# 1PCB_Shematic.net
KiCad netlist of a schematic drawn in Altium Designer
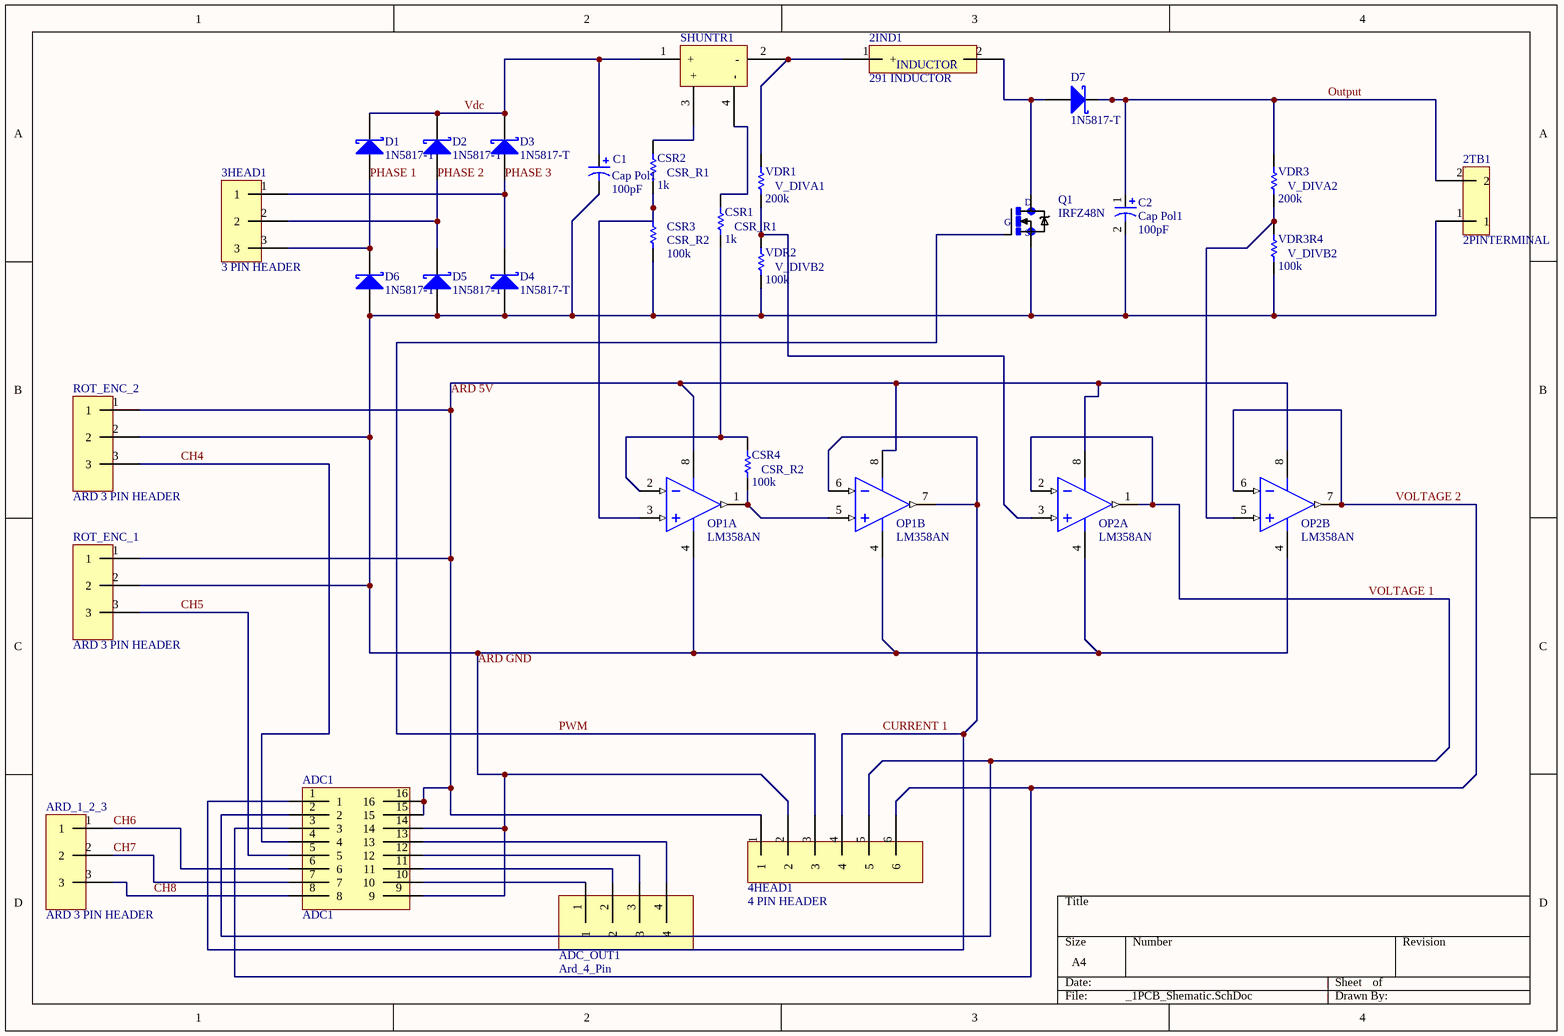
[diagram p0: _1PCB_Shematic.SchDoc]

(export (version "E")
  (design (tool "Eeschema 10.0.6"))
  (components
    (comp (ref "2IND1")
      (value "291 INDUCTOR")
      (footprint "3 CM INDUCTOR")
      (libsource (lib "CUSTOM IND") (part "2IND?"))
    )
    (comp (ref "2TB1")
      (value "2PINTERMINAL")
      (footprint "2 PIN TERMINAL BLOCK")
      (libsource (lib "altium-import") (part "root_1_2TB?_"))
    )
    (comp (ref "3HEAD1")
      (value "3 PIN HEADER")
      (footprint "3 PIN HEADER")
      (libsource (lib "3PINHEADER") (part "3HEAD?"))
    )
    (comp (ref "4HEAD1")
      (value "4 PIN HEADER")
      (footprint "4 PIN HEADER")
      (libsource (lib "4PINHEADER") (part "4HEAD?"))
    )
    (comp (ref "ADC1")
      (value "ADC1")
      (footprint "PDIP16_300MC")
      (libsource (lib "altium-import") (part "root_0_MCP3008_"))
    )
    (comp (ref "ADC_OUT1")
      (value "Ard_4_Pin")
      (footprint "ARD_4_PIN")
      (libsource (lib "altium-import") (part "root_0_APIN?_"))
    )
    (comp (ref "ARD_1_2_3")
      (value "ARD 3 PIN HEADER")
      (footprint "ARD 3 PIN HEADER")
      (libsource (lib "altium-import") (part "root_3_ARD_3_PIN?_"))
    )
    (comp (ref "C1")
      (value "Cap Pol1")
      (footprint "PCBComponent_1")
      (description "Polarized Capacitor (Radial)")
      (fields (field (name "ALTIUM_VALUE") "100pF") (field (name "PUBLISHER") "Altium Limited"))
      (libsource (lib "") (part "Cap Pol1_1"))
    )
    (comp (ref "C2")
      (value "Cap Pol1")
      (footprint "Copy of cap:PCBComponent_1")
      (description "Polarized Capacitor (Radial)")
      (fields (field (name "ALTIUM_VALUE") "100pF") (field (name "PUBLISHER") "Altium Limited"))
      (libsource (lib "Miscellaneous Devices") (part "Cap Pol1"))
    )
    (comp (ref "CSR1")
      (value "CSR_R1")
      (footprint "AXIAL-0.3")
      (description "Resistor")
      (fields (field (name "ALTIUM_VALUE") "1k") (field (name "PUBLISHER") "Altium Limited"))
      (libsource (lib "Miscellaneous Devices") (part "Res1"))
    )
    (comp (ref "CSR2")
      (value "CSR_R1")
      (footprint "AXIAL-0.3")
      (description "Resistor")
      (fields (field (name "ALTIUM_VALUE") "1k") (field (name "PUBLISHER") "Altium Limited"))
      (libsource (lib "Miscellaneous Devices") (part "Res1"))
    )
    (comp (ref "CSR3")
      (value "CSR_R2")
      (footprint "AXIAL-0.3")
      (description "Resistor")
      (fields (field (name "ALTIUM_VALUE") "100k") (field (name "PUBLISHER") "Altium Limited"))
      (libsource (lib "Miscellaneous Devices") (part "Res1"))
    )
    (comp (ref "CSR4")
      (value "CSR_R2")
      (footprint "AXIAL-0.3")
      (description "Resistor")
      (fields (field (name "ALTIUM_VALUE") "100k") (field (name "PUBLISHER") "Altium Limited"))
      (libsource (lib "Miscellaneous Devices") (part "Res1"))
    )
    (comp (ref "D1")
      (value "1N5817-T")
      (footprint "DIOD-DO-41-P-2")
      (description "Schottky Barrier Rectifier, 1 A, 20 V, -65 to 125 degC, 2-Pin DO-41, RoHS, Tape and Reel")
      (fields (field (name "MANUFACTURER") "DiodesIncorporated"))
      (libsource (lib "Altium Content Vault") (part "DSKY-AK-2"))
    )
    (comp (ref "D2")
      (value "1N5817-T")
      (footprint "DIOD-DO-41-P-2")
      (description "Schottky Barrier Rectifier, 1 A, 20 V, -65 to 125 degC, 2-Pin DO-41, RoHS, Tape and Reel")
      (fields (field (name "MANUFACTURER") "DiodesIncorporated"))
      (libsource (lib "Altium Content Vault") (part "DSKY-AK-2"))
    )
    (comp (ref "D3")
      (value "1N5817-T")
      (footprint "DIOD-DO-41-P-2")
      (description "Schottky Barrier Rectifier, 1 A, 20 V, -65 to 125 degC, 2-Pin DO-41, RoHS, Tape and Reel")
      (fields (field (name "MANUFACTURER") "DiodesIncorporated"))
      (libsource (lib "Altium Content Vault") (part "DSKY-AK-2"))
    )
    (comp (ref "D4")
      (value "1N5817-T")
      (footprint "DIOD-DO-41-P-2")
      (description "Schottky Barrier Rectifier, 1 A, 20 V, -65 to 125 degC, 2-Pin DO-41, RoHS, Tape and Reel")
      (fields (field (name "MANUFACTURER") "DiodesIncorporated"))
      (libsource (lib "Altium Content Vault") (part "DSKY-AK-2"))
    )
    (comp (ref "D5")
      (value "1N5817-T")
      (footprint "DIOD-DO-41-P-2")
      (description "Schottky Barrier Rectifier, 1 A, 20 V, -65 to 125 degC, 2-Pin DO-41, RoHS, Tape and Reel")
      (fields (field (name "MANUFACTURER") "DiodesIncorporated"))
      (libsource (lib "Altium Content Vault") (part "DSKY-AK-2"))
    )
    (comp (ref "D6")
      (value "1N5817-T")
      (footprint "DIOD-DO-41-P-2")
      (description "Schottky Barrier Rectifier, 1 A, 20 V, -65 to 125 degC, 2-Pin DO-41, RoHS, Tape and Reel")
      (fields (field (name "MANUFACTURER") "DiodesIncorporated"))
      (libsource (lib "Altium Content Vault") (part "DSKY-AK-2"))
    )
    (comp (ref "D7")
      (value "1N5817-T")
      (footprint "DIOD-DO-41-P-2")
      (description "Schottky Barrier Rectifier, 1 A, 20 V, -65 to 125 degC, 2-Pin DO-41, RoHS, Tape and Reel")
      (fields (field (name "MANUFACTURER") "DiodesIncorporated"))
      (libsource (lib "Altium Content Vault") (part "DSKY-AK-2"))
    )
    (comp (ref "OP1")
      (value "LM358AN")
      (footprint "N08E")
      (description "Low Power Dual Operational Amplifier, 8-pin MDIP")
      (fields (field (name "MANUFACTURER") "National Semiconductor"))
      (libsource (lib "Altium Content Vault") (part "AMP-OPA-LM158-8"))
    )
    (comp (ref "OP2")
      (value "LM358AN")
      (footprint "N08E")
      (description "Low Power Dual Operational Amplifier, 8-pin MDIP")
      (fields (field (name "MANUFACTURER") "National Semiconductor"))
      (libsource (lib "Altium Content Vault") (part "AMP-OPA-LM158-8"))
    )
    (comp (ref "Q1")
      (value "IRFZ48N")
      (footprint "TO220BV_IRFZ48N(Primary)")
      (description "55V Single N-Channel HEXFET Power MOSFET in a TO-220AB package")
      (fields (field (name "MF") "International Rectifier"))
      (libsource (lib "IRFZ48N") (part "IRFZ48N"))
    )
    (comp (ref "ROT_ENC_1")
      (value "ARD 3 PIN HEADER")
      (footprint "ARD 3 PIN HEADER")
      (libsource (lib "altium-import") (part "root_3_ARD_3_PIN?_"))
    )
    (comp (ref "ROT_ENC_2")
      (value "ARD 3 PIN HEADER")
      (footprint "ARD 3 PIN HEADER")
      (libsource (lib "altium-import") (part "root_3_ARD_3_PIN?_"))
    )
    (comp (ref "SHUNTR1")
      (value "~")
      (footprint "SHUNT15.24")
      (libsource (lib "SHUNT RESISTOR") (part "SHUNTR?"))
    )
    (comp (ref "VDR1")
      (value "V_DIVA1")
      (footprint "AXIAL-0.3")
      (description "Resistor")
      (fields (field (name "ALTIUM_VALUE") "200k") (field (name "PUBLISHER") "Altium Limited"))
      (libsource (lib "Miscellaneous Devices") (part "Res1"))
    )
    (comp (ref "VDR2")
      (value "V_DIVB2")
      (footprint "AXIAL-0.3")
      (description "Resistor")
      (fields (field (name "ALTIUM_VALUE") "100k") (field (name "PUBLISHER") "Altium Limited"))
      (libsource (lib "Miscellaneous Devices") (part "Res1"))
    )
    (comp (ref "VDR3")
      (value "V_DIVA2")
      (footprint "AXIAL-0.3")
      (description "Resistor")
      (fields (field (name "ALTIUM_VALUE") "200k") (field (name "PUBLISHER") "Altium Limited"))
      (libsource (lib "Miscellaneous Devices") (part "Res1"))
    )
    (comp (ref "VDR3R4")
      (value "V_DIVB2")
      (footprint "AXIAL-0.3")
      (description "Resistor")
      (fields (field (name "ALTIUM_VALUE") "100k") (field (name "PUBLISHER") "Altium Limited"))
      (libsource (lib "Miscellaneous Devices") (part "Res1"))
    )
  )
  (nets
    (net (code "1") (name "/ARD 5V") (class "Default")
      (node (ref "4HEAD1") (pin "1") (pinfunction "1_1") (pintype "passive"))
      (node (ref "ADC1") (pin "15") (pinfunction "15_15") (pintype "passive"))
      (node (ref "ADC1") (pin "16") (pinfunction "16_16") (pintype "passive"))
      (node (ref "OP1") (pin "8") (pinfunction "V+_8") (pintype "power_in"))
      (node (ref "OP2") (pin "8") (pinfunction "V+_8") (pintype "power_in"))
      (node (ref "ROT_ENC_1") (pin "1") (pinfunction "1_1") (pintype "passive"))
      (node (ref "ROT_ENC_2") (pin "1") (pinfunction "1_1") (pintype "passive"))
    )
    (net (code "2") (name "/ARD GND") (class "Default")
      (node (ref "2TB1") (pin "1") (pinfunction "1_1") (pintype "passive"))
      (node (ref "4HEAD1") (pin "2") (pinfunction "2_2") (pintype "passive"))
      (node (ref "ADC1") (pin "14") (pinfunction "14_14") (pintype "passive"))
      (node (ref "ADC1") (pin "9") (pinfunction "9_9") (pintype "passive"))
      (node (ref "C1") (pin "2") (pinfunction "2_2") (pintype "passive"))
      (node (ref "C2") (pin "2") (pinfunction "2_2") (pintype "passive"))
      (node (ref "CSR3") (pin "2") (pinfunction "2_2") (pintype "passive"))
      (node (ref "D4") (pin "1") (pinfunction "A_1") (pintype "passive"))
      (node (ref "D5") (pin "1") (pinfunction "A_1") (pintype "passive"))
      (node (ref "D6") (pin "1") (pinfunction "A_1") (pintype "passive"))
      (node (ref "OP1") (pin "4") (pinfunction "GND_4") (pintype "power_in"))
      (node (ref "OP2") (pin "4") (pinfunction "GND_4") (pintype "power_in"))
      (node (ref "Q1") (pin "S") (pinfunction "S_S") (pintype "passive"))
      (node (ref "ROT_ENC_1") (pin "2") (pinfunction "2_2") (pintype "passive"))
      (node (ref "ROT_ENC_2") (pin "2") (pinfunction "2_2") (pintype "passive"))
      (node (ref "VDR2") (pin "2") (pinfunction "2_2") (pintype "passive"))
      (node (ref "VDR3R4") (pin "2") (pinfunction "2_2") (pintype "passive"))
    )
    (net (code "3") (name "/CH4") (class "Default")
      (node (ref "ADC1") (pin "4") (pinfunction "4_4") (pintype "passive"))
      (node (ref "ROT_ENC_2") (pin "3") (pinfunction "3_3") (pintype "passive"))
    )
    (net (code "4") (name "/CH5") (class "Default")
      (node (ref "ADC1") (pin "5") (pinfunction "5_5") (pintype "passive"))
      (node (ref "ROT_ENC_1") (pin "3") (pinfunction "3_3") (pintype "passive"))
    )
    (net (code "5") (name "/CH6") (class "Default")
      (node (ref "ADC1") (pin "6") (pinfunction "6_6") (pintype "passive"))
      (node (ref "ARD_1_2_3") (pin "1") (pinfunction "1_1") (pintype "passive"))
    )
    (net (code "6") (name "/CH7") (class "Default")
      (node (ref "ADC1") (pin "7") (pinfunction "7_7") (pintype "passive"))
      (node (ref "ARD_1_2_3") (pin "2") (pinfunction "2_2") (pintype "passive"))
    )
    (net (code "7") (name "/CH8") (class "Default")
      (node (ref "ADC1") (pin "8") (pinfunction "8_8") (pintype "passive"))
      (node (ref "ARD_1_2_3") (pin "3") (pinfunction "3_3") (pintype "passive"))
    )
    (net (code "8") (name "/CURRENT 1") (class "Default")
      (node (ref "4HEAD1") (pin "4") (pinfunction "4_4") (pintype "passive"))
      (node (ref "ADC1") (pin "1") (pinfunction "1_1") (pintype "passive"))
      (node (ref "OP1") (pin "6") (pinfunction "INB-_6") (pintype "input"))
      (node (ref "OP1") (pin "7") (pinfunction "OUTB_7") (pintype "output"))
    )
    (net (code "9") (name "/Output") (class "Default")
      (node (ref "2TB1") (pin "2") (pinfunction "2_2") (pintype "passive"))
      (node (ref "C2") (pin "1") (pinfunction "1_1") (pintype "passive"))
      (node (ref "D7") (pin "2") (pinfunction "K_2") (pintype "passive"))
      (node (ref "VDR3") (pin "1") (pinfunction "1_1") (pintype "passive"))
    )
    (net (code "10") (name "/PHASE 1") (class "Default")
      (node (ref "3HEAD1") (pin "3") (pinfunction "3_3") (pintype "passive"))
      (node (ref "D1") (pin "1") (pinfunction "A_1") (pintype "passive"))
      (node (ref "D6") (pin "2") (pinfunction "K_2") (pintype "passive"))
    )
    (net (code "11") (name "/PHASE 2") (class "Default")
      (node (ref "3HEAD1") (pin "2") (pinfunction "2_2") (pintype "passive"))
      (node (ref "D2") (pin "1") (pinfunction "A_1") (pintype "passive"))
      (node (ref "D5") (pin "2") (pinfunction "K_2") (pintype "passive"))
    )
    (net (code "12") (name "/PHASE 3") (class "Default")
      (node (ref "3HEAD1") (pin "1") (pinfunction "1_1") (pintype "passive"))
      (node (ref "D3") (pin "1") (pinfunction "A_1") (pintype "passive"))
      (node (ref "D4") (pin "2") (pinfunction "K_2") (pintype "passive"))
    )
    (net (code "13") (name "/PWM") (class "Default")
      (node (ref "4HEAD1") (pin "3") (pinfunction "3_3") (pintype "passive"))
      (node (ref "Q1") (pin "G") (pinfunction "G_G") (pintype "passive"))
    )
    (net (code "14") (name "/VOLTAGE 1") (class "Default")
      (node (ref "4HEAD1") (pin "5") (pinfunction "5_5") (pintype "passive"))
      (node (ref "ADC1") (pin "2") (pinfunction "2_2") (pintype "passive"))
      (node (ref "OP2") (pin "1") (pinfunction "OUTA_1") (pintype "output"))
      (node (ref "OP2") (pin "2") (pinfunction "INA-_2") (pintype "input"))
    )
    (net (code "15") (name "/VOLTAGE 2") (class "Default")
      (node (ref "4HEAD1") (pin "6") (pinfunction "6_6") (pintype "passive"))
      (node (ref "ADC1") (pin "3") (pinfunction "3_3") (pintype "passive"))
      (node (ref "OP2") (pin "6") (pinfunction "INB-_6") (pintype "input"))
      (node (ref "OP2") (pin "7") (pinfunction "OUTB_7") (pintype "output"))
    )
    (net (code "16") (name "/Vdc") (class "Default")
      (node (ref "C1") (pin "1") (pinfunction "1_1") (pintype "passive"))
      (node (ref "D1") (pin "2") (pinfunction "K_2") (pintype "passive"))
      (node (ref "D2") (pin "2") (pinfunction "K_2") (pintype "passive"))
      (node (ref "D3") (pin "2") (pinfunction "K_2") (pintype "passive"))
      (node (ref "SHUNTR1") (pin "1") (pinfunction "+_1") (pintype "passive"))
    )
    (net (code "17") (name "Net-(2IND1-+)") (class "Default")
      (node (ref "2IND1") (pin "1") (pinfunction "+_1") (pintype "passive"))
      (node (ref "SHUNTR1") (pin "2") (pinfunction "-_2") (pintype "passive"))
      (node (ref "VDR1") (pin "1") (pinfunction "1_1") (pintype "passive"))
    )
    (net (code "18") (name "Net-(2IND1--)") (class "Default")
      (node (ref "2IND1") (pin "2") (pinfunction "-_2") (pintype "passive"))
      (node (ref "D7") (pin "1") (pinfunction "A_1") (pintype "passive"))
      (node (ref "Q1") (pin "D") (pinfunction "D_D") (pintype "passive"))
    )
    (net (code "19") (name "Net-(ADC1-Pad10)") (class "Default")
      (node (ref "ADC1") (pin "10") (pinfunction "10_10") (pintype "passive"))
      (node (ref "ADC_OUT1") (pin "1") (pinfunction "1_1") (pintype "passive"))
    )
    (net (code "20") (name "Net-(ADC1-Pad11)") (class "Default")
      (node (ref "ADC1") (pin "11") (pinfunction "11_11") (pintype "passive"))
      (node (ref "ADC_OUT1") (pin "2") (pinfunction "2_2") (pintype "passive"))
    )
    (net (code "21") (name "Net-(ADC1-Pad12)") (class "Default")
      (node (ref "ADC1") (pin "12") (pinfunction "12_12") (pintype "passive"))
      (node (ref "ADC_OUT1") (pin "3") (pinfunction "3_3") (pintype "passive"))
    )
    (net (code "22") (name "Net-(ADC1-Pad13)") (class "Default")
      (node (ref "ADC1") (pin "13") (pinfunction "13_13") (pintype "passive"))
      (node (ref "ADC_OUT1") (pin "4") (pinfunction "4_4") (pintype "passive"))
    )
    (net (code "23") (name "Net-(CSR1-Pad2)") (class "Default")
      (node (ref "CSR1") (pin "2") (pinfunction "2_2") (pintype "passive"))
      (node (ref "SHUNTR1") (pin "4") (pinfunction "-_4") (pintype "passive"))
    )
    (net (code "24") (name "Net-(CSR2-Pad2)") (class "Default")
      (node (ref "CSR2") (pin "2") (pinfunction "2_2") (pintype "passive"))
      (node (ref "SHUNTR1") (pin "3") (pinfunction "+_3") (pintype "passive"))
    )
    (net (code "25") (name "Net-(OP1A-INA+)") (class "Default")
      (node (ref "CSR2") (pin "1") (pinfunction "1_1") (pintype "passive"))
      (node (ref "CSR3") (pin "1") (pinfunction "1_1") (pintype "passive"))
      (node (ref "OP1") (pin "3") (pinfunction "INA+_3") (pintype "input"))
    )
    (net (code "26") (name "Net-(OP1A-INA-)") (class "Default")
      (node (ref "CSR1") (pin "1") (pinfunction "1_1") (pintype "passive"))
      (node (ref "CSR4") (pin "1") (pinfunction "1_1") (pintype "passive"))
      (node (ref "OP1") (pin "2") (pinfunction "INA-_2") (pintype "input"))
    )
    (net (code "27") (name "Net-(OP1A-OUTA)") (class "Default")
      (node (ref "CSR4") (pin "2") (pinfunction "2_2") (pintype "passive"))
      (node (ref "OP1") (pin "1") (pinfunction "OUTA_1") (pintype "output"))
      (node (ref "OP1") (pin "5") (pinfunction "INB+_5") (pintype "input"))
    )
    (net (code "28") (name "Net-(OP2A-INA+)") (class "Default")
      (node (ref "OP2") (pin "3") (pinfunction "INA+_3") (pintype "input"))
      (node (ref "VDR1") (pin "2") (pinfunction "2_2") (pintype "passive"))
      (node (ref "VDR2") (pin "1") (pinfunction "1_1") (pintype "passive"))
    )
    (net (code "29") (name "Net-(OP2B-INB+)") (class "Default")
      (node (ref "OP2") (pin "5") (pinfunction "INB+_5") (pintype "input"))
      (node (ref "VDR3") (pin "2") (pinfunction "2_2") (pintype "passive"))
      (node (ref "VDR3R4") (pin "1") (pinfunction "1_1") (pintype "passive"))
    )
  )
)
